# AlienWhoopF7.net
KiCad netlist of a schematic drawn in EAGLE
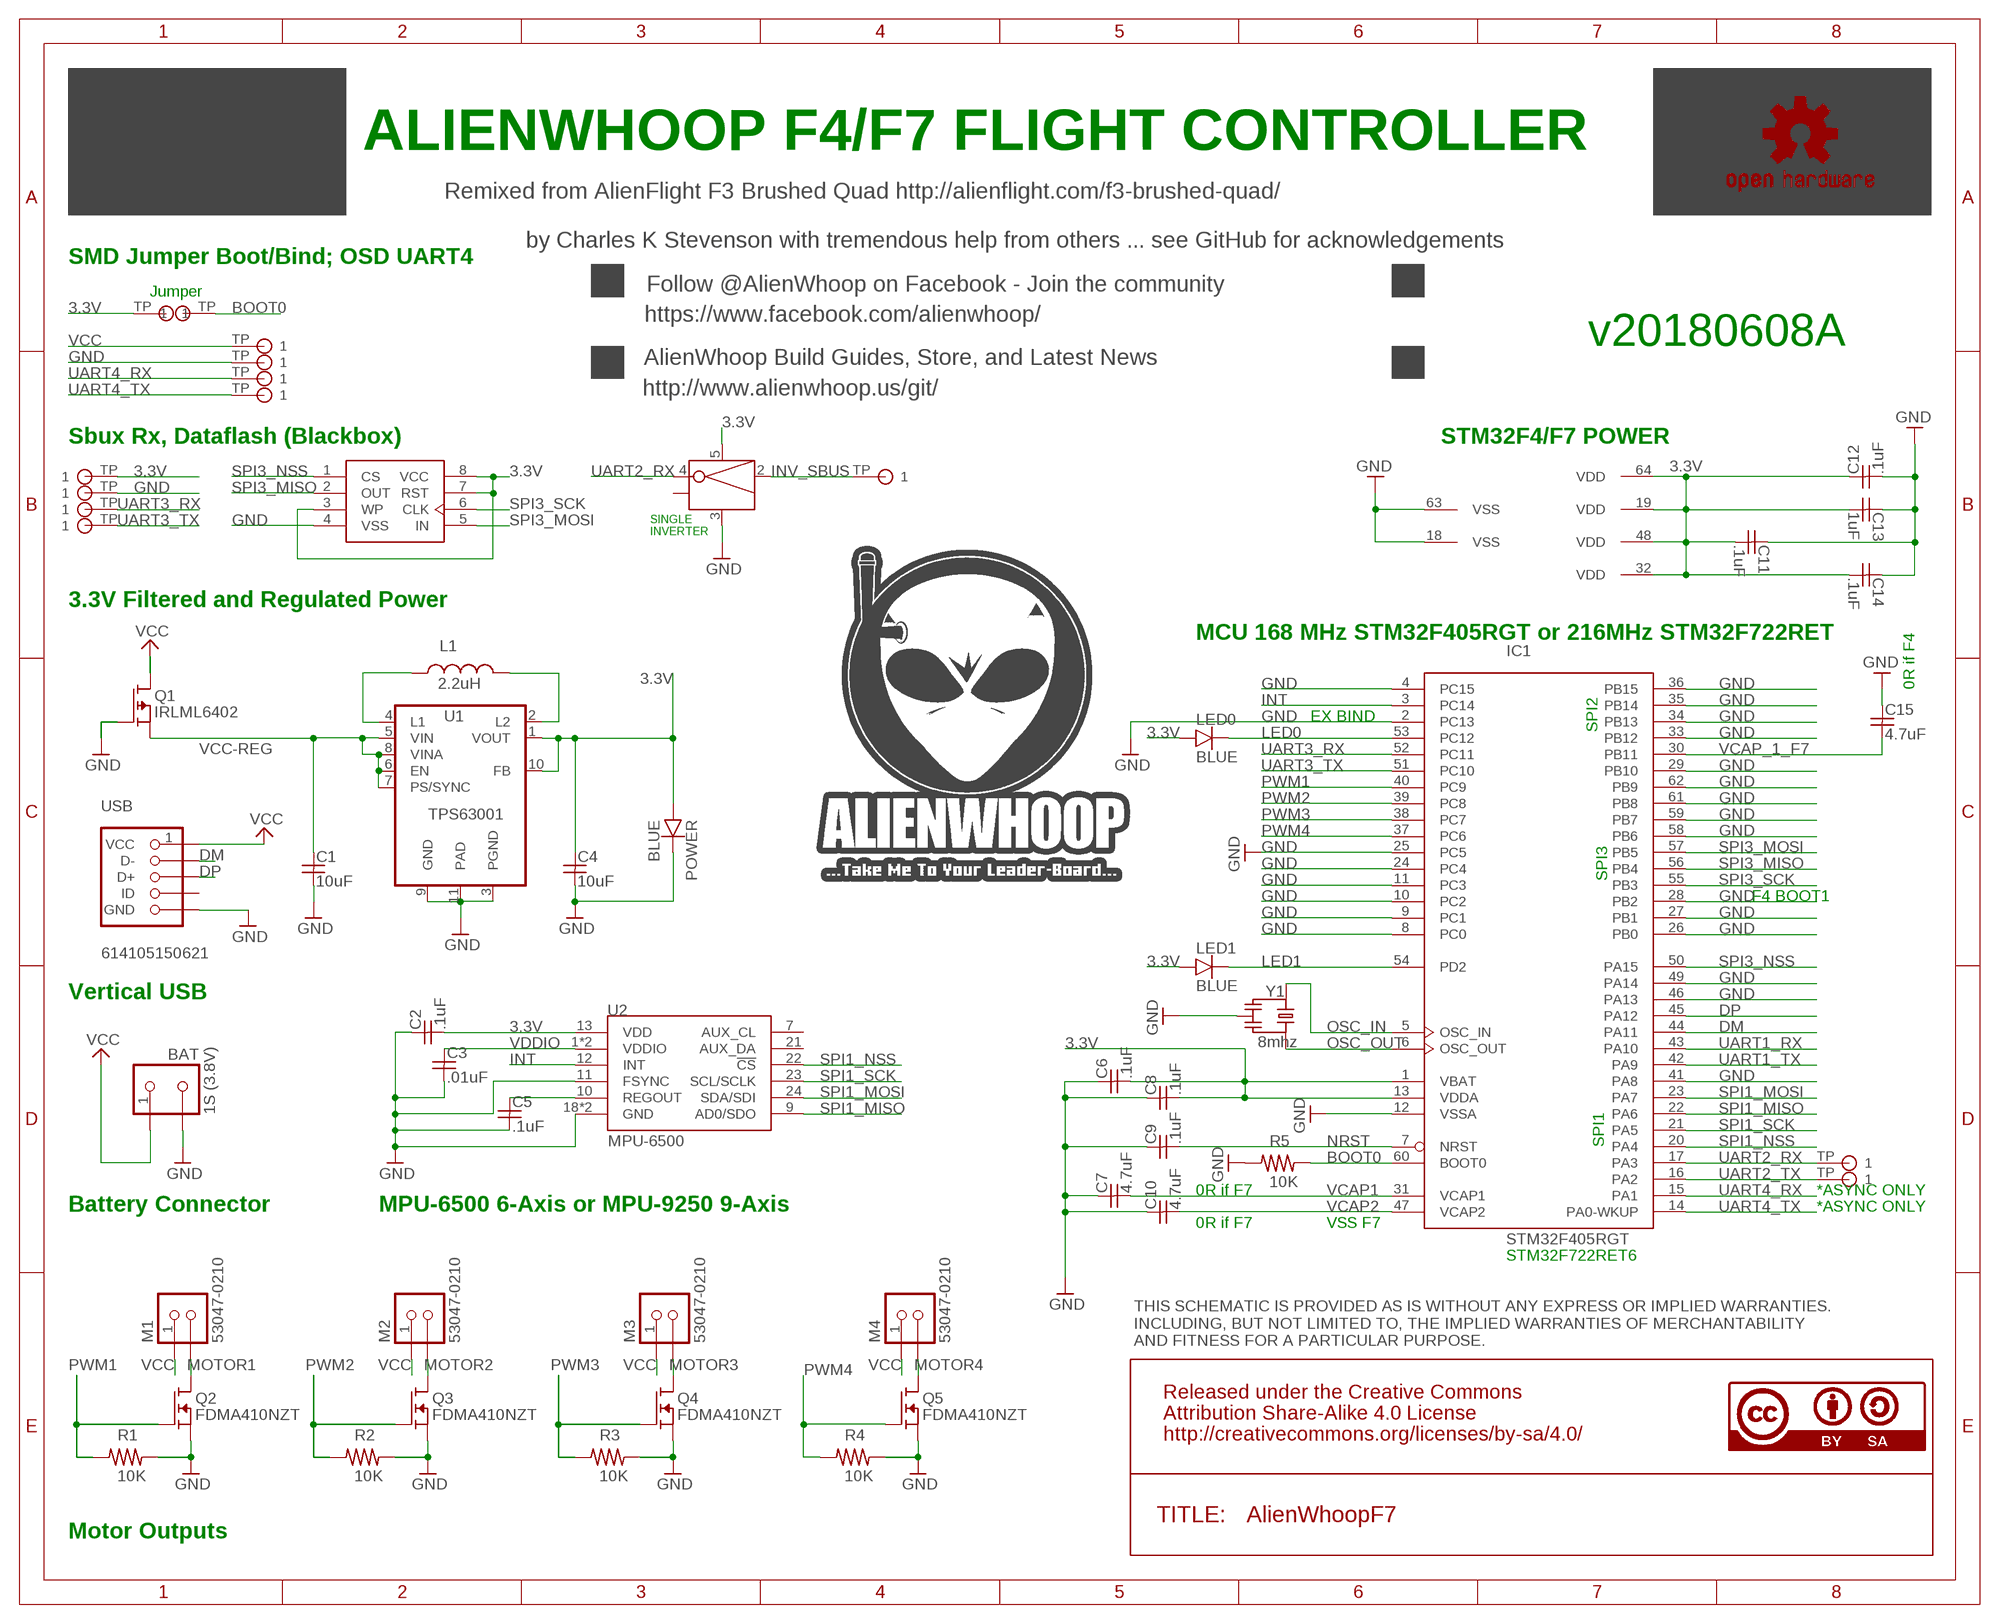
[diagram p0: schematic, sheet 1]

(export (version "E")
  (design (tool "Eeschema 10.0.6"))
  (components
    (comp (ref "3.3V")
      (value "TESTPAD")
      (footprint "eagle-import:TESTPAD")
      (libsource (lib "eagle-import") (part "TESTPAD"))
    )
    (comp (ref "3V3")
      (value "TESTPAD")
      (footprint "eagle-import:TESTPAD")
      (libsource (lib "eagle-import") (part "TESTPAD"))
    )
    (comp (ref "BAT")
      (value "1S (3.8V)")
      (footprint "eagle-import:S2B-PH-K-S")
      (fields (field (name "MF") "JST") (field (name "MPN") "S2B-PH-K-S"))
      (libsource (lib "eagle-import") (part "JST-PH-BAT"))
    )
    (comp (ref "BOOT")
      (value "TESTPAD")
      (footprint "eagle-import:TESTPAD")
      (libsource (lib "eagle-import") (part "TESTPAD"))
    )
    (comp (ref "C1")
      (value "10uF")
      (footprint "eagle-import:YUDEN-CAP-0805")
      (fields (field (name "MF") "Taiyo Yuden") (field (name "MPN") "JMK212AB7106KG-T"))
      (libsource (lib "eagle-import") (part "CAPACITOR10UF"))
    )
    (comp (ref "C2")
      (value ".1uF")
      (footprint "eagle-import:MUR-CAP-0603")
      (fields (field (name "MF") "Murata") (field (name "MPN") "GRM188R71C104KA01D"))
      (libsource (lib "eagle-import") (part "CAPACITOR.1UF"))
    )
    (comp (ref "C3")
      (value ".01uF")
      (footprint "eagle-import:MUR-CAP-0603")
      (fields (field (name "MF") "Murata") (field (name "MPN") "GRM188R71C103KA01D"))
      (libsource (lib "eagle-import") (part "CAPACITOR.01UF"))
    )
    (comp (ref "C4")
      (value "10uF")
      (footprint "eagle-import:YUDEN-CAP-0805")
      (fields (field (name "MF") "Taiyo Yuden") (field (name "MPN") "JMK212AB7106KG-T"))
      (libsource (lib "eagle-import") (part "CAPACITOR10UF"))
    )
    (comp (ref "C5")
      (value ".1uF")
      (footprint "eagle-import:MUR-CAP-0603")
      (fields (field (name "MF") "Murata") (field (name "MPN") "GRM188R71C104KA01D"))
      (libsource (lib "eagle-import") (part "CAPACITOR.1UF"))
    )
    (comp (ref "C6")
      (value ".1uF")
      (footprint "eagle-import:MUR-CAP-0603")
      (fields (field (name "MF") "Murata") (field (name "MPN") "GRM188R71C104KA01D"))
      (libsource (lib "eagle-import") (part "CAPACITOR.1UF"))
    )
    (comp (ref "C7")
      (value "4.7uF")
      (footprint "eagle-import:MUR-CAP-0603")
      (fields (field (name "MF") "Murata") (field (name "MPN") "GRJ188C70J475KE11D"))
      (libsource (lib "eagle-import") (part "CAPACITOR4.7UF"))
    )
    (comp (ref "C8")
      (value ".1uF")
      (footprint "eagle-import:MUR-CAP-0603")
      (fields (field (name "MF") "Murata") (field (name "MPN") "GRM188R71C104KA01D"))
      (libsource (lib "eagle-import") (part "CAPACITOR.1UF"))
    )
    (comp (ref "C9")
      (value ".1uF")
      (footprint "eagle-import:MUR-CAP-0603")
      (fields (field (name "MF") "Murata") (field (name "MPN") "GRM188R71C104KA01D"))
      (libsource (lib "eagle-import") (part "CAPACITOR.1UF"))
    )
    (comp (ref "C10")
      (value "4.7uF")
      (footprint "eagle-import:MUR-CAP-0603")
      (fields (field (name "MF") "Murata") (field (name "MPN") "GRJ188C70J475KE11D"))
      (libsource (lib "eagle-import") (part "CAPACITOR4.7UF"))
    )
    (comp (ref "C11")
      (value ".1uF")
      (footprint "eagle-import:MUR-CAP-0603")
      (fields (field (name "MF") "Murata") (field (name "MPN") "GRM188R71C104KA01D"))
      (libsource (lib "eagle-import") (part "CAPACITOR.1UF"))
    )
    (comp (ref "C12")
      (value ".1uF")
      (footprint "eagle-import:MUR-CAP-0603")
      (fields (field (name "MF") "Murata") (field (name "MPN") "GRM188R71C104KA01D"))
      (libsource (lib "eagle-import") (part "CAPACITOR.1UF"))
    )
    (comp (ref "C13")
      (value "1uF")
      (footprint "eagle-import:MUR-CAP-0603")
      (fields (field (name "MF") "Murata") (field (name "MPN") "GRM188R71C105KA12D"))
      (libsource (lib "eagle-import") (part "CAPACITOR1UF"))
    )
    (comp (ref "C14")
      (value ".1uF")
      (footprint "eagle-import:MUR-CAP-0603")
      (fields (field (name "MF") "Murata") (field (name "MPN") "GRM188R71C104KA01D"))
      (libsource (lib "eagle-import") (part "CAPACITOR.1UF"))
    )
    (comp (ref "C15")
      (value "4.7uF")
      (footprint "eagle-import:MUR-CAP-0603")
      (fields (field (name "MF") "Murata") (field (name "MPN") "GRJ188C70J475KE11D"))
      (libsource (lib "eagle-import") (part "CAPACITOR4.7UF"))
    )
    (comp (ref "GND")
      (value "TESTPAD")
      (footprint "eagle-import:TESTPAD")
      (libsource (lib "eagle-import") (part "TESTPAD"))
    )
    (comp (ref "GND@1")
      (value "TESTPAD")
      (footprint "eagle-import:TESTPAD")
      (libsource (lib "eagle-import") (part "TESTPAD"))
    )
    (comp (ref "IC1")
      (value "STM32F405RGT")
      (footprint "eagle-import:LQFP64")
      (fields (field (name "MPN") "STM32F045RGT"))
      (libsource (lib "eagle-import") (part "STM32F405RTG"))
    )
    (comp (ref "L1")
      (value "2.2uH")
      (footprint "eagle-import:DFE201612E-2R2M-P2")
      (fields (field (name "PARTNO") "DFE201612E-2R2M-P2"))
      (libsource (lib "eagle-import") (part "DFE201612E-2R2M-P2"))
    )
    (comp (ref "LED0")
      (value "BLUE")
      (footprint "eagle-import:SMD-CHIP-LED-0805")
      (fields (field (name "MF") "Kingbright") (field (name "MPN") "APHCM2012QBC/D-F01"))
      (libsource (lib "eagle-import") (part "SMD-CHIP-LED-0805"))
    )
    (comp (ref "LED1")
      (value "BLUE")
      (footprint "eagle-import:SMD-CHIP-LED-0805")
      (fields (field (name "MF") "Kingbright") (field (name "MPN") "APHCM2012QBC/D-F01"))
      (libsource (lib "eagle-import") (part "SMD-CHIP-LED-0805"))
    )
    (comp (ref "LOGO3")
      (value "OSHW-LOGOS")
      (footprint "eagle-import:OSHW-LOGO-S")
      (libsource (lib "eagle-import") (part "OSHW-LOGOS"))
    )
    (comp (ref "M1")
      (value "53047-0210")
      (footprint "eagle-import:PICO-53047-02")
      (fields (field (name "MF") "MOLEX"))
      (libsource (lib "eagle-import") (part "PICO-1.25-MOTOR"))
    )
    (comp (ref "M2")
      (value "53047-0210")
      (footprint "eagle-import:PICO-53047-02")
      (fields (field (name "MF") "MOLEX"))
      (libsource (lib "eagle-import") (part "PICO-1.25-MOTOR"))
    )
    (comp (ref "M3")
      (value "53047-0210")
      (footprint "eagle-import:PICO-53047-02")
      (fields (field (name "MF") "MOLEX"))
      (libsource (lib "eagle-import") (part "PICO-1.25-MOTOR"))
    )
    (comp (ref "M4")
      (value "53047-0210")
      (footprint "eagle-import:PICO-53047-02")
      (fields (field (name "MF") "MOLEX"))
      (libsource (lib "eagle-import") (part "PICO-1.25-MOTOR"))
    )
    (comp (ref "POWER")
      (value "BLUE")
      (footprint "eagle-import:SMD-CHIP-LED-0805")
      (fields (field (name "MF") "Kingbright") (field (name "MPN") "APHCM2012QBC/D-F01"))
      (libsource (lib "eagle-import") (part "SMD-CHIP-LED-0805"))
    )
    (comp (ref "Q1")
      (value "IRLML6402")
      (footprint "eagle-import:SOT-23")
      (fields (field (name "MF") "IR"))
      (libsource (lib "eagle-import") (part "MOSFET-P"))
    )
    (comp (ref "Q2")
      (value "FDMA410NZT")
      (footprint "eagle-import:MICROFET-2X2")
      (fields (field (name "MF") "Fairchild") (field (name "MPN") "FDMA410NZ"))
      (libsource (lib "eagle-import") (part "FDMA410NZ"))
    )
    (comp (ref "Q3")
      (value "FDMA410NZT")
      (footprint "eagle-import:MICROFET-2X2")
      (fields (field (name "MF") "Fairchild") (field (name "MPN") "FDMA410NZ"))
      (libsource (lib "eagle-import") (part "FDMA410NZ"))
    )
    (comp (ref "Q4")
      (value "FDMA410NZT")
      (footprint "eagle-import:MICROFET-2X2")
      (fields (field (name "MF") "Fairchild") (field (name "MPN") "FDMA410NZ"))
      (libsource (lib "eagle-import") (part "FDMA410NZ"))
    )
    (comp (ref "Q5")
      (value "FDMA410NZT")
      (footprint "eagle-import:MICROFET-2X2")
      (fields (field (name "MF") "Fairchild") (field (name "MPN") "FDMA410NZ"))
      (libsource (lib "eagle-import") (part "FDMA410NZ"))
    )
    (comp (ref "R1")
      (value "10K")
      (footprint "eagle-import:VISH-RES-0603")
      (fields (field (name "MF") "Vishay") (field (name "MPN") "CRCW060310K0FKEAHP"))
      (libsource (lib "eagle-import") (part "RESISTOR10K"))
    )
    (comp (ref "R2")
      (value "10K")
      (footprint "eagle-import:VISH-RES-0603")
      (fields (field (name "MF") "Vishay") (field (name "MPN") "CRCW060310K0FKEAHP"))
      (libsource (lib "eagle-import") (part "RESISTOR10K"))
    )
    (comp (ref "R3")
      (value "10K")
      (footprint "eagle-import:VISH-RES-0603")
      (fields (field (name "MF") "Vishay") (field (name "MPN") "CRCW060310K0FKEAHP"))
      (libsource (lib "eagle-import") (part "RESISTOR10K"))
    )
    (comp (ref "R4")
      (value "10K")
      (footprint "eagle-import:VISH-RES-0603")
      (fields (field (name "MF") "Vishay") (field (name "MPN") "CRCW060310K0FKEAHP"))
      (libsource (lib "eagle-import") (part "RESISTOR10K"))
    )
    (comp (ref "R5")
      (value "10K")
      (footprint "eagle-import:VISH-RES-0603")
      (fields (field (name "MF") "Vishay") (field (name "MPN") "CRCW060310K0FKEAHP"))
      (libsource (lib "eagle-import") (part "RESISTOR10K"))
    )
    (comp (ref "RX2")
      (value "TESTPAD")
      (footprint "eagle-import:TESTPAD")
      (libsource (lib "eagle-import") (part "TESTPAD"))
    )
    (comp (ref "RX2/INV")
      (value "TESTPAD")
      (footprint "eagle-import:TESTPAD")
      (libsource (lib "eagle-import") (part "TESTPAD"))
    )
    (comp (ref "RX3")
      (value "TESTPAD")
      (footprint "eagle-import:TESTPAD")
      (libsource (lib "eagle-import") (part "TESTPAD"))
    )
    (comp (ref "RX4")
      (value "TESTPAD")
      (footprint "eagle-import:TESTPAD")
      (libsource (lib "eagle-import") (part "TESTPAD"))
    )
    (comp (ref "TX2")
      (value "TESTPAD")
      (footprint "eagle-import:TESTPAD")
      (libsource (lib "eagle-import") (part "TESTPAD"))
    )
    (comp (ref "TX3")
      (value "TESTPAD")
      (footprint "eagle-import:TESTPAD")
      (libsource (lib "eagle-import") (part "TESTPAD"))
    )
    (comp (ref "TX4")
      (value "TESTPAD")
      (footprint "eagle-import:TESTPAD")
      (libsource (lib "eagle-import") (part "TESTPAD"))
    )
    (comp (ref "U1")
      (value "TPS63001")
      (footprint "eagle-import:VSON-N10")
      (fields (field (name "MF") "TI") (field (name "MPN") "TPS63001DRCR"))
      (libsource (lib "eagle-import") (part "TPS630XX-TPS63001"))
    )
    (comp (ref "U2")
      (value "MPU-6500")
      (footprint "eagle-import:QFN24_PAD")
      (libsource (lib "eagle-import") (part "MPU-9250"))
    )
    (comp (ref "U3")
      (value "MX25L6406EM2I-12G")
      (footprint "eagle-import:M25P32")
      (libsource (lib "eagle-import") (part "M25P32"))
    )
    (comp (ref "U4")
      (value "SN74LVC1G04DBVR")
      (footprint "eagle-import:SOT23-5")
      (libsource (lib "eagle-import") (part "SN74LVC1G04"))
    )
    (comp (ref "USB")
      (value "614105150621")
      (footprint "eagle-import:USB-BFPV")
      (libsource (lib "eagle-import") (part "MICROUSBUSB-BFPV"))
    )
    (comp (ref "VCC@1")
      (value "TESTPAD")
      (footprint "eagle-import:TESTPAD")
      (libsource (lib "eagle-import") (part "TESTPAD"))
    )
    (comp (ref "Y1")
      (value "8mhz")
      (footprint "eagle-import:RESONATOR_8")
      (fields (field (name "MF") "Murata") (field (name "MPN") "CSTCE8M00G55-R0"))
      (libsource (lib "eagle-import") (part "RESONATOR8MHZ"))
    )
  )
  (nets
    (net (code "1") (name "/3.3V") (class "Default")
      (node (ref "3.3V") (pin "TP") (pinfunction "1_TP") (pintype "bidirectional"))
      (node (ref "3V3") (pin "TP") (pinfunction "1_TP") (pintype "bidirectional"))
      (node (ref "C11") (pin "2") (pinfunction "2_2") (pintype "passive"))
      (node (ref "C12") (pin "1") (pinfunction "1_1") (pintype "passive"))
      (node (ref "C13") (pin "2") (pinfunction "2_2") (pintype "passive"))
      (node (ref "C14") (pin "2") (pinfunction "2_2") (pintype "passive"))
      (node (ref "C2") (pin "2") (pinfunction "2_2") (pintype "passive"))
      (node (ref "C4") (pin "1") (pinfunction "1_1") (pintype "passive"))
      (node (ref "C6") (pin "2") (pinfunction "2_2") (pintype "passive"))
      (node (ref "C8") (pin "2") (pinfunction "2_2") (pintype "passive"))
      (node (ref "IC1") (pin "1") (pinfunction "VBAT_1") (pintype "power_in"))
      (node (ref "IC1") (pin "13") (pinfunction "VDDA_13") (pintype "power_in"))
      (node (ref "IC1") (pin "19") (pinfunction "VDD_19") (pintype "power_in"))
      (node (ref "IC1") (pin "32") (pinfunction "VDD_32") (pintype "power_in"))
      (node (ref "IC1") (pin "48") (pinfunction "VDD_48") (pintype "power_in"))
      (node (ref "IC1") (pin "64") (pinfunction "VDD_64") (pintype "power_in"))
      (node (ref "LED0") (pin "A") (pinfunction "A_A") (pintype "passive"))
      (node (ref "LED1") (pin "A") (pinfunction "A_A") (pintype "passive"))
      (node (ref "POWER") (pin "A") (pinfunction "A_A") (pintype "passive"))
      (node (ref "U1") (pin "1") (pinfunction "VOUT_1") (pintype "bidirectional"))
      (node (ref "U1") (pin "10") (pinfunction "FB_10") (pintype "bidirectional"))
      (node (ref "U2") (pin "13") (pinfunction "VDD_13") (pintype "bidirectional"))
      (node (ref "U3") (pin "3") (pinfunction "WP_3") (pintype "bidirectional"))
      (node (ref "U3") (pin "7") (pinfunction "RST_7") (pintype "bidirectional"))
      (node (ref "U3") (pin "8") (pinfunction "VCC_8") (pintype "power_in"))
      (node (ref "U4") (pin "5") (pinfunction "VCC_5") (pintype "power_in"))
    )
    (net (code "2") (name "/BOOT0") (class "Default")
      (node (ref "BOOT") (pin "TP") (pinfunction "1_TP") (pintype "bidirectional"))
      (node (ref "IC1") (pin "60") (pinfunction "BOOT0_60") (pintype "input"))
      (node (ref "R5") (pin "1") (pinfunction "1_1") (pintype "passive"))
    )
    (net (code "3") (name "/DM") (class "Default")
      (node (ref "IC1") (pin "44") (pinfunction "PA11_44") (pintype "bidirectional"))
      (node (ref "USB") (pin "2") (pinfunction "D-_2") (pintype "passive"))
    )
    (net (code "4") (name "/DP") (class "Default")
      (node (ref "IC1") (pin "45") (pinfunction "PA12_45") (pintype "bidirectional"))
      (node (ref "USB") (pin "3") (pinfunction "D+_3") (pintype "passive"))
    )
    (net (code "5") (name "/INT") (class "Default")
      (node (ref "IC1") (pin "3") (pinfunction "PC14_3") (pintype "bidirectional"))
      (node (ref "U2") (pin "12") (pinfunction "INT_12") (pintype "bidirectional"))
    )
    (net (code "6") (name "/INV_SBUS") (class "Default")
      (node (ref "RX2/INV") (pin "TP") (pinfunction "1_TP") (pintype "bidirectional"))
      (node (ref "U4") (pin "2") (pinfunction "A_2") (pintype "input"))
    )
    (net (code "7") (name "/LED0") (class "Default")
      (node (ref "IC1") (pin "53") (pinfunction "PC12_53") (pintype "bidirectional"))
      (node (ref "LED0") (pin "C") (pinfunction "C_C") (pintype "passive"))
    )
    (net (code "8") (name "/LED1") (class "Default")
      (node (ref "IC1") (pin "54") (pinfunction "PD2_54") (pintype "bidirectional"))
      (node (ref "LED1") (pin "C") (pinfunction "C_C") (pintype "passive"))
    )
    (net (code "9") (name "/MOTOR1") (class "Default")
      (node (ref "M1") (pin "2") (pinfunction "2_2") (pintype "passive"))
      (node (ref "Q2") (pin "D") (pinfunction "D_D") (pintype "bidirectional"))
      (node (ref "Q2") (pin "D1") (pinfunction "D_D1") (pintype "bidirectional"))
      (node (ref "Q2") (pin "D2") (pinfunction "D_D2") (pintype "bidirectional"))
      (node (ref "Q2") (pin "D3") (pinfunction "D_D3") (pintype "bidirectional"))
      (node (ref "Q2") (pin "D4") (pinfunction "D_D4") (pintype "bidirectional"))
    )
    (net (code "10") (name "/MOTOR2") (class "Default")
      (node (ref "M2") (pin "2") (pinfunction "2_2") (pintype "passive"))
      (node (ref "Q3") (pin "D") (pinfunction "D_D") (pintype "bidirectional"))
      (node (ref "Q3") (pin "D1") (pinfunction "D_D1") (pintype "bidirectional"))
      (node (ref "Q3") (pin "D2") (pinfunction "D_D2") (pintype "bidirectional"))
      (node (ref "Q3") (pin "D3") (pinfunction "D_D3") (pintype "bidirectional"))
      (node (ref "Q3") (pin "D4") (pinfunction "D_D4") (pintype "bidirectional"))
    )
    (net (code "11") (name "/MOTOR3") (class "Default")
      (node (ref "M3") (pin "2") (pinfunction "2_2") (pintype "passive"))
      (node (ref "Q4") (pin "D") (pinfunction "D_D") (pintype "bidirectional"))
      (node (ref "Q4") (pin "D1") (pinfunction "D_D1") (pintype "bidirectional"))
      (node (ref "Q4") (pin "D2") (pinfunction "D_D2") (pintype "bidirectional"))
      (node (ref "Q4") (pin "D3") (pinfunction "D_D3") (pintype "bidirectional"))
      (node (ref "Q4") (pin "D4") (pinfunction "D_D4") (pintype "bidirectional"))
    )
    (net (code "12") (name "/MOTOR4") (class "Default")
      (node (ref "M4") (pin "2") (pinfunction "2_2") (pintype "passive"))
      (node (ref "Q5") (pin "D") (pinfunction "D_D") (pintype "bidirectional"))
      (node (ref "Q5") (pin "D1") (pinfunction "D_D1") (pintype "bidirectional"))
      (node (ref "Q5") (pin "D2") (pinfunction "D_D2") (pintype "bidirectional"))
      (node (ref "Q5") (pin "D3") (pinfunction "D_D3") (pintype "bidirectional"))
      (node (ref "Q5") (pin "D4") (pinfunction "D_D4") (pintype "bidirectional"))
    )
    (net (code "13") (name "/NRST") (class "Default")
      (node (ref "C9") (pin "2") (pinfunction "2_2") (pintype "passive"))
      (node (ref "IC1") (pin "7") (pinfunction "NRST_7") (pintype "bidirectional"))
    )
    (net (code "14") (name "/OSC_IN") (class "Default")
      (node (ref "IC1") (pin "5") (pinfunction "OSC_IN_5") (pintype "bidirectional"))
      (node (ref "Y1") (pin "1") (pinfunction "1_1") (pintype "passive"))
    )
    (net (code "15") (name "/OSC_OUT") (class "Default")
      (node (ref "IC1") (pin "6") (pinfunction "OSC_OUT_6") (pintype "bidirectional"))
      (node (ref "Y1") (pin "3") (pinfunction "3_3") (pintype "passive"))
    )
    (net (code "16") (name "/PWM1") (class "Default")
      (node (ref "IC1") (pin "40") (pinfunction "PC9_40") (pintype "bidirectional"))
      (node (ref "Q2") (pin "G") (pinfunction "G_G") (pintype "bidirectional"))
      (node (ref "R1") (pin "2") (pinfunction "2_2") (pintype "passive"))
    )
    (net (code "17") (name "/PWM2") (class "Default")
      (node (ref "IC1") (pin "39") (pinfunction "PC8_39") (pintype "bidirectional"))
      (node (ref "Q3") (pin "G") (pinfunction "G_G") (pintype "bidirectional"))
      (node (ref "R2") (pin "2") (pinfunction "2_2") (pintype "passive"))
    )
    (net (code "18") (name "/PWM3") (class "Default")
      (node (ref "IC1") (pin "38") (pinfunction "PC7_38") (pintype "bidirectional"))
      (node (ref "Q4") (pin "G") (pinfunction "G_G") (pintype "bidirectional"))
      (node (ref "R3") (pin "2") (pinfunction "2_2") (pintype "passive"))
    )
    (net (code "19") (name "/PWM4") (class "Default")
      (node (ref "IC1") (pin "37") (pinfunction "PC6_37") (pintype "bidirectional"))
      (node (ref "Q5") (pin "G") (pinfunction "G_G") (pintype "bidirectional"))
      (node (ref "R4") (pin "2") (pinfunction "2_2") (pintype "passive"))
    )
    (net (code "20") (name "/SPI1_MISO") (class "Default")
      (node (ref "IC1") (pin "22") (pinfunction "PA6_22") (pintype "bidirectional"))
      (node (ref "U2") (pin "9") (pinfunction "AD0/SDO_9") (pintype "bidirectional"))
    )
    (net (code "21") (name "/SPI1_MOSI") (class "Default")
      (node (ref "IC1") (pin "23") (pinfunction "PA7_23") (pintype "bidirectional"))
      (node (ref "U2") (pin "24") (pinfunction "SDA/SDI_24") (pintype "bidirectional"))
    )
    (net (code "22") (name "/SPI1_NSS") (class "Default")
      (node (ref "IC1") (pin "20") (pinfunction "PA4_20") (pintype "bidirectional"))
      (node (ref "U2") (pin "22") (pinfunction "~{CS}_22") (pintype "bidirectional"))
    )
    (net (code "23") (name "/SPI1_SCK") (class "Default")
      (node (ref "IC1") (pin "21") (pinfunction "PA5_21") (pintype "bidirectional"))
      (node (ref "U2") (pin "23") (pinfunction "SCL/SCLK_23") (pintype "bidirectional"))
    )
    (net (code "24") (name "/SPI3_MISO") (class "Default")
      (node (ref "IC1") (pin "56") (pinfunction "PB4_56") (pintype "bidirectional"))
      (node (ref "U3") (pin "2") (pinfunction "OUT_2") (pintype "output"))
    )
    (net (code "25") (name "/SPI3_MOSI") (class "Default")
      (node (ref "IC1") (pin "57") (pinfunction "PB5_57") (pintype "bidirectional"))
      (node (ref "U3") (pin "5") (pinfunction "IN_5") (pintype "input"))
    )
    (net (code "26") (name "/SPI3_NSS") (class "Default")
      (node (ref "IC1") (pin "50") (pinfunction "PA15_50") (pintype "bidirectional"))
      (node (ref "U3") (pin "1") (pinfunction "CS_1") (pintype "bidirectional"))
    )
    (net (code "27") (name "/SPI3_SCK") (class "Default")
      (node (ref "IC1") (pin "55") (pinfunction "PB3_55") (pintype "bidirectional"))
      (node (ref "U3") (pin "6") (pinfunction "CLK_6") (pintype "bidirectional"))
    )
    (net (code "28") (name "/UART1_RX") (class "Default")
      (node (ref "IC1") (pin "43") (pinfunction "PA10_43") (pintype "bidirectional"))
    )
    (net (code "29") (name "/UART1_TX") (class "Default")
      (node (ref "IC1") (pin "42") (pinfunction "PA9_42") (pintype "bidirectional"))
    )
    (net (code "30") (name "/UART2_RX") (class "Default")
      (node (ref "IC1") (pin "17") (pinfunction "PA3_17") (pintype "bidirectional"))
      (node (ref "RX2") (pin "TP") (pinfunction "1_TP") (pintype "bidirectional"))
      (node (ref "U4") (pin "4") (pinfunction "Y_4") (pintype "output"))
    )
    (net (code "31") (name "/UART2_TX") (class "Default")
      (node (ref "IC1") (pin "16") (pinfunction "PA2_16") (pintype "bidirectional"))
      (node (ref "TX2") (pin "TP") (pinfunction "1_TP") (pintype "bidirectional"))
    )
    (net (code "32") (name "/UART3_RX") (class "Default")
      (node (ref "IC1") (pin "52") (pinfunction "PC11_52") (pintype "bidirectional"))
      (node (ref "RX3") (pin "TP") (pinfunction "1_TP") (pintype "bidirectional"))
    )
    (net (code "33") (name "/UART3_TX") (class "Default")
      (node (ref "IC1") (pin "51") (pinfunction "PC10_51") (pintype "bidirectional"))
      (node (ref "TX3") (pin "TP") (pinfunction "1_TP") (pintype "bidirectional"))
    )
    (net (code "34") (name "/UART4_RX") (class "Default")
      (node (ref "IC1") (pin "15") (pinfunction "PA1_15") (pintype "bidirectional"))
      (node (ref "RX4") (pin "TP") (pinfunction "1_TP") (pintype "bidirectional"))
    )
    (net (code "35") (name "/UART4_TX") (class "Default")
      (node (ref "IC1") (pin "14") (pinfunction "PA0-WKUP_14") (pintype "bidirectional"))
      (node (ref "TX4") (pin "TP") (pinfunction "1_TP") (pintype "bidirectional"))
    )
    (net (code "36") (name "/VCAP1") (class "Default")
      (node (ref "C7") (pin "2") (pinfunction "2_2") (pintype "passive"))
      (node (ref "IC1") (pin "31") (pinfunction "VCAP1_31") (pintype "power_in"))
    )
    (net (code "37") (name "/VCAP2") (class "Default")
      (node (ref "C10") (pin "2") (pinfunction "2_2") (pintype "passive"))
      (node (ref "IC1") (pin "47") (pinfunction "VCAP2_47") (pintype "power_in"))
    )
    (net (code "38") (name "/VCAP_1_F7") (class "Default")
      (node (ref "C15") (pin "2") (pinfunction "2_2") (pintype "passive"))
      (node (ref "IC1") (pin "30") (pinfunction "PB11_30") (pintype "bidirectional"))
    )
    (net (code "39") (name "/VCC-REG") (class "Default")
      (node (ref "C1") (pin "1") (pinfunction "1_1") (pintype "passive"))
      (node (ref "Q1") (pin "2") (pinfunction "S_2") (pintype "bidirectional"))
      (node (ref "U1") (pin "5") (pinfunction "VIN_5") (pintype "bidirectional"))
      (node (ref "U1") (pin "6") (pinfunction "EN_6") (pintype "bidirectional"))
      (node (ref "U1") (pin "7") (pinfunction "PS/SYNC_7") (pintype "bidirectional"))
      (node (ref "U1") (pin "8") (pinfunction "VINA_8") (pintype "bidirectional"))
    )
    (net (code "40") (name "/VDDIO") (class "Default")
      (node (ref "C3") (pin "1") (pinfunction "1_1") (pintype "passive"))
      (node (ref "U2") (pin "1") (pinfunction "VDDIO_1") (pintype "bidirectional"))
      (node (ref "U2") (pin "8") (pinfunction "VDDIO_8") (pintype "bidirectional"))
    )
    (net (code "41") (name "GND") (class "Default")
      (node (ref "BAT") (pin "2") (pinfunction "2_2") (pintype "bidirectional"))
      (node (ref "C1") (pin "2") (pinfunction "2_2") (pintype "passive"))
      (node (ref "C10") (pin "1") (pinfunction "1_1") (pintype "passive"))
      (node (ref "C11") (pin "1") (pinfunction "1_1") (pintype "passive"))
      (node (ref "C12") (pin "2") (pinfunction "2_2") (pintype "passive"))
      (node (ref "C13") (pin "1") (pinfunction "1_1") (pintype "passive"))
      (node (ref "C14") (pin "1") (pinfunction "1_1") (pintype "passive"))
      (node (ref "C15") (pin "1") (pinfunction "1_1") (pintype "passive"))
      (node (ref "C2") (pin "1") (pinfunction "1_1") (pintype "passive"))
      (node (ref "C3") (pin "2") (pinfunction "2_2") (pintype "passive"))
      (node (ref "C4") (pin "2") (pinfunction "2_2") (pintype "passive"))
      (node (ref "C5") (pin "2") (pinfunction "2_2") (pintype "passive"))
      (node (ref "C6") (pin "1") (pinfunction "1_1") (pintype "passive"))
      (node (ref "C7") (pin "1") (pinfunction "1_1") (pintype "passive"))
      (node (ref "C8") (pin "1") (pinfunction "1_1") (pintype "passive"))
      (node (ref "C9") (pin "1") (pinfunction "1_1") (pintype "passive"))
      (node (ref "GND") (pin "TP") (pinfunction "1_TP") (pintype "bidirectional"))
      (node (ref "GND@1") (pin "TP") (pinfunction "1_TP") (pintype "bidirectional"))
      (node (ref "IC1") (pin "10") (pinfunction "PC2_10") (pintype "bidirectional"))
      (node (ref "IC1") (pin "11") (pinfunction "PC3_11") (pintype "bidirectional"))
      (node (ref "IC1") (pin "12") (pinfunction "VSSA_12") (pintype "power_in"))
      (node (ref "IC1") (pin "18") (pinfunction "VSS_18") (pintype "power_in"))
      (node (ref "IC1") (pin "2") (pinfunction "PC13_2") (pintype "bidirectional"))
      (node (ref "IC1") (pin "24") (pinfunction "PC4_24") (pintype "bidirectional"))
      (node (ref "IC1") (pin "25") (pinfunction "PC5_25") (pintype "bidirectional"))
      (node (ref "IC1") (pin "26") (pinfunction "PB0_26") (pintype "bidirectional"))
      (node (ref "IC1") (pin "27") (pinfunction "PB1_27") (pintype "bidirectional"))
      (node (ref "IC1") (pin "28") (pinfunction "PB2_28") (pintype "bidirectional"))
      (node (ref "IC1") (pin "29") (pinfunction "PB10_29") (pintype "bidirectional"))
      (node (ref "IC1") (pin "33") (pinfunction "PB12_33") (pintype "bidirectional"))
      (node (ref "IC1") (pin "34") (pinfunction "PB13_34") (pintype "bidirectional"))
      (node (ref "IC1") (pin "35") (pinfunction "PB14_35") (pintype "bidirectional"))
      (node (ref "IC1") (pin "36") (pinfunction "PB15_36") (pintype "bidirectional"))
      (node (ref "IC1") (pin "4") (pinfunction "PC15_4") (pintype "bidirectional"))
      (node (ref "IC1") (pin "41") (pinfunction "PA8_41") (pintype "bidirectional"))
      (node (ref "IC1") (pin "46") (pinfunction "PA13_46") (pintype "bidirectional"))
      (node (ref "IC1") (pin "49") (pinfunction "PA14_49") (pintype "bidirectional"))
      (node (ref "IC1") (pin "58") (pinfunction "PB6_58") (pintype "bidirectional"))
      (node (ref "IC1") (pin "59") (pinfunction "PB7_59") (pintype "bidirectional"))
      (node (ref "IC1") (pin "61") (pinfunction "PB8_61") (pintype "bidirectional"))
      (node (ref "IC1") (pin "62") (pinfunction "PB9_62") (pintype "bidirectional"))
      (node (ref "IC1") (pin "63") (pinfunction "VSS_63") (pintype "power_in"))
      (node (ref "IC1") (pin "8") (pinfunction "PC0_8") (pintype "bidirectional"))
      (node (ref "IC1") (pin "9") (pinfunction "PC1_9") (pintype "bidirectional"))
      (node (ref "POWER") (pin "C") (pinfunction "C_C") (pintype "passive"))
      (node (ref "Q1") (pin "1") (pinfunction "G_1") (pintype "bidirectional"))
      (node (ref "Q2") (pin "S") (pinfunction "S_S") (pintype "bidirectional"))
      (node (ref "Q2") (pin "S1") (pinfunction "S_S1") (pintype "bidirectional"))
      (node (ref "Q3") (pin "S") (pinfunction "S_S") (pintype "bidirectional"))
      (node (ref "Q3") (pin "S1") (pinfunction "S_S1") (pintype "bidirectional"))
      (node (ref "Q4") (pin "S") (pinfunction "S_S") (pintype "bidirectional"))
      (node (ref "Q4") (pin "S1") (pinfunction "S_S1") (pintype "bidirectional"))
      (node (ref "Q5") (pin "S") (pinfunction "S_S") (pintype "bidirectional"))
      (node (ref "Q5") (pin "S1") (pinfunction "S_S1") (pintype "bidirectional"))
      (node (ref "R1") (pin "1") (pinfunction "1_1") (pintype "passive"))
      (node (ref "R2") (pin "1") (pinfunction "1_1") (pintype "passive"))
      (node (ref "R3") (pin "1") (pinfunction "1_1") (pintype "passive"))
      (node (ref "R4") (pin "1") (pinfunction "1_1") (pintype "passive"))
      (node (ref "R5") (pin "2") (pinfunction "2_2") (pintype "passive"))
      (node (ref "U1") (pin "11") (pinfunction "PAD_11") (pintype "bidirectional"))
      (node (ref "U1") (pin "3") (pinfunction "PGND_3") (pintype "bidirectional"))
      (node (ref "U1") (pin "9") (pinfunction "GND_9") (pintype "bidirectional"))
      (node (ref "U2") (pin "11") (pinfunction "FSYNC_11") (pintype "bidirectional"))
      (node (ref "U2") (pin "18") (pinfunction "GND_18") (pintype "bidirectional"))
      (node (ref "U2") (pin "20") (pinfunction "GND_20") (pintype "bidirectional"))
      (node (ref "U3") (pin "4") (pinfunction "VSS_4") (pintype "power_in"))
      (node (ref "U4") (pin "3") (pinfunction "GND_3") (pintype "power_in"))
      (node (ref "USB") (pin "5") (pinfunction "GND_5") (pintype "passive"))
      (node (ref "USB") (pin "P$6") (pinfunction "GND_P$6") (pintype "passive"))
      (node (ref "USB") (pin "P$7") (pinfunction "GND_P$7") (pintype "passive"))
      (node (ref "Y1") (pin "2") (pinfunction "2_2") (pintype "passive"))
    )
    (net (code "42") (name "Net-(L1-1)") (class "Default")
      (node (ref "L1") (pin "P$1") (pinfunction "1_P$1") (pintype "passive"))
      (node (ref "U1") (pin "4") (pinfunction "L1_4") (pintype "bidirectional"))
    )
    (net (code "43") (name "Net-(L1-2)") (class "Default")
      (node (ref "L1") (pin "P$2") (pinfunction "2_P$2") (pintype "passive"))
      (node (ref "U1") (pin "2") (pinfunction "L2_2") (pintype "bidirectional"))
    )
    (net (code "44") (name "Net-(U2-REGOUT)") (class "Default")
      (node (ref "C5") (pin "1") (pinfunction "1_1") (pintype "passive"))
      (node (ref "U2") (pin "10") (pinfunction "REGOUT_10") (pintype "bidirectional"))
    )
    (net (code "45") (name "VCC") (class "Default")
      (node (ref "BAT") (pin "1") (pinfunction "1_1") (pintype "bidirectional"))
      (node (ref "M1") (pin "1") (pinfunction "1_1") (pintype "passive"))
      (node (ref "M2") (pin "1") (pinfunction "1_1") (pintype "passive"))
      (node (ref "M3") (pin "1") (pinfunction "1_1") (pintype "passive"))
      (node (ref "M4") (pin "1") (pinfunction "1_1") (pintype "passive"))
      (node (ref "Q1") (pin "3") (pinfunction "D_3") (pintype "bidirectional"))
      (node (ref "USB") (pin "1") (pinfunction "VCC_1") (pintype "passive"))
      (node (ref "VCC@1") (pin "TP") (pinfunction "1_TP") (pintype "bidirectional"))
    )
    (net (code "46") (name "unconnected-(U2-AUX_CL-Pad7)") (class "Default")
      (node (ref "U2") (pin "7") (pinfunction "AUX_CL_7") (pintype "bidirectional"))
    )
    (net (code "47") (name "unconnected-(U2-AUX_DA-Pad21)") (class "Default")
      (node (ref "U2") (pin "21") (pinfunction "AUX_DA_21") (pintype "bidirectional"))
    )
    (net (code "48") (name "unconnected-(U4-Pad1)") (class "Default")
      (node (ref "U4") (pin "1") (pinfunction "1_1") (pintype "no_connect"))
    )
    (net (code "49") (name "unconnected-(USB-ID-Pad4)") (class "Default")
      (node (ref "USB") (pin "4") (pinfunction "ID_4") (pintype "passive"))
    )
  )
)
